# AMU-S03-V00-PSU3V5.net
KiCad netlist of a schematic drawn in Altium Designer
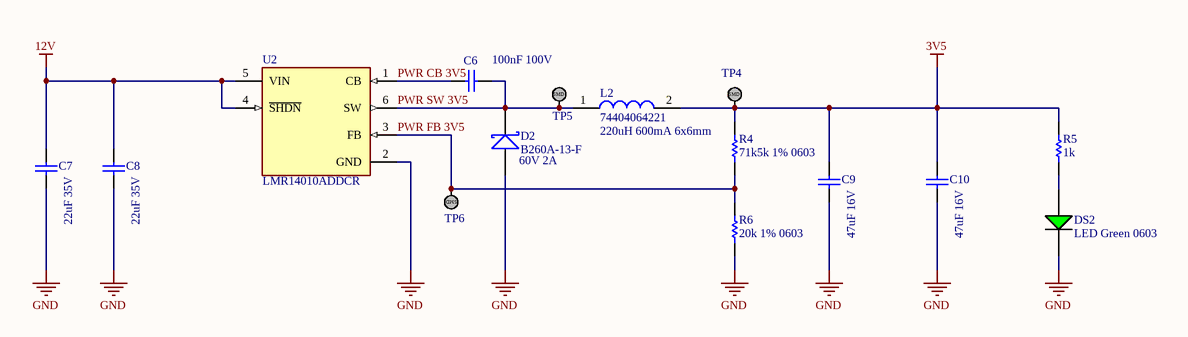
[diagram p0: AMU-S03-V00-PSU3V5.SchDoc]

(export (version "E")
  (design (tool "Eeschema 10.0.6"))
  (components
    (comp (ref "C6")
      (value "100nF 100V")
      (footprint "Cap_Ceramic_0603")
      (description "Capacitor, Ceramic, SMD, 100nF, 100V, 5%, X7R, 0603")
      (libsource (lib "StandardCapacitors") (part "100nF 100V 5% X7R 0603"))
    )
    (comp (ref "C7")
      (value "22uF 35V")
      (footprint "Cap_Ceramic_1206")
      (description "22µF ±20% 35V Ceramic Capacitor X5R 1206 (3216 Metric)")
      (libsource (lib "StandardCapacitors") (part "22uF 35V 20% X5R 1206"))
    )
    (comp (ref "C8")
      (value "22uF 35V")
      (footprint "Cap_Ceramic_1206")
      (description "22µF ±20% 35V Ceramic Capacitor X5R 1206 (3216 Metric)")
      (libsource (lib "StandardCapacitors") (part "22uF 35V 20% X5R 1206"))
    )
    (comp (ref "C9")
      (value "47uF 16V")
      (footprint "Cap_Ceramic_0603")
      (description "Capacitor, Ceramic, SMD, 47uF, 16V, 5%, X7R, 1210")
      (libsource (lib "StandardCapacitors") (part "47uF 16V 10% X7R 1210"))
    )
    (comp (ref "C10")
      (value "47uF 16V")
      (footprint "Cap_Ceramic_0603")
      (description "Capacitor, Ceramic, SMD, 47uF, 16V, 5%, X7R, 1210")
      (libsource (lib "StandardCapacitors") (part "47uF 16V 10% X7R 1210"))
    )
    (comp (ref "D2")
      (value "B260A-13-F")
      (footprint "SMA")
      (description "Diode, Schottky Barrier Rectifier, 60 V, 2 A, B260A-13-F")
      (libsource (lib "QUTMS_DiodeLibrary") (part "B260A-13-F"))
    )
    (comp (ref "DS2")
      (value "LED Green 0603")
      (footprint "LED GREEN 0603")
      (libsource (lib "QUTMS_LEDLibrary") (part "LED Green 0603"))
    )
    (comp (ref "L2")
      (value "74404064221")
      (footprint "Inductor_6x6mm")
      (description "FIXED IND 220UH 660MA 850 MOHM")
      (libsource (lib "QUTMS_InductorLibrary") (part "74404064221"))
    )
    (comp (ref "R4")
      (value "71k5k 1% 0603")
      (footprint "Res_ThinFilm_0603")
      (description "Resistor, SMD, 71k5, 0.1W, 1%, 0603")
      (libsource (lib "StandardResistors") (part "71k5 1% 0603"))
    )
    (comp (ref "R5")
      (value "1k")
      (footprint "Res_ThinFilm_0603")
      (description "Resistor, SMD, 1k, 0.1W, 5%, 0603")
      (libsource (lib "StandardResistors") (part "1k 5% 0603"))
    )
    (comp (ref "R6")
      (value "20k 1% 0603")
      (footprint "Res_ThinFilm_0603")
      (description "Resistor, SMD, 20k, 0.1W, 1%, 0603")
      (libsource (lib "StandardResistors") (part "20k 1% 0603"))
    )
    (comp (ref "TP4")
      (value "TestPoint_SMD")
      (footprint "TestPointSMD")
      (libsource (lib "StandardTest") (part "TestPoint_SMD"))
    )
    (comp (ref "TP5")
      (value "TestPoint_SMD")
      (footprint "TestPointSMD")
      (libsource (lib "StandardTest") (part "TestPoint_SMD"))
    )
    (comp (ref "TP6")
      (value "TestPoint_SMD")
      (footprint "TestPointSMD")
      (libsource (lib "StandardTest") (part "TestPoint_SMD"))
    )
    (comp (ref "U2")
      (value "LMR14010ADDCR")
      (footprint "FP-DDC0006A-MFG")
      (description "IC REG BUCK ADJ 1A TSOT23-6")
      (fields
        (field (name "MANUFACTURER") "Texas Instruments")
        (field (name "OCTOPART") "https://octopart.com/lmr14010addcr-texas+instruments-90753290")
      )
      (libsource (lib "Altium Content Vault") (part "248534993f007311ab4e1890f26e637"))
    )
  )
  (nets
    (net (code "1") (name "/PWR CB 3V5") (class "Default")
      (node (ref "C6") (pin "1") (pinfunction "1_1") (pintype "passive"))
      (node (ref "U2") (pin "1") (pinfunction "CB_1") (pintype "input"))
    )
    (net (code "2") (name "/PWR FB 3V5") (class "Default")
      (node (ref "R4") (pin "1") (pinfunction "1_1") (pintype "passive"))
      (node (ref "R6") (pin "2") (pinfunction "2_2") (pintype "passive"))
      (node (ref "TP6") (pin "1") (pinfunction "1_1") (pintype "passive"))
      (node (ref "U2") (pin "3") (pinfunction "FB_3") (pintype "input"))
    )
    (net (code "3") (name "/PWR SW 3V5") (class "Default")
      (node (ref "C6") (pin "2") (pinfunction "2_2") (pintype "passive"))
      (node (ref "D2") (pin "K") (pinfunction "K_K") (pintype "passive"))
      (node (ref "L2") (pin "1") (pinfunction "1_1") (pintype "passive"))
      (node (ref "TP5") (pin "1") (pinfunction "1_1") (pintype "passive"))
      (node (ref "U2") (pin "6") (pinfunction "SW_6") (pintype "output"))
    )
    (net (code "4") (name "3V5") (class "Default")
      (node (ref "C10") (pin "2") (pinfunction "2_2") (pintype "passive"))
      (node (ref "C9") (pin "2") (pinfunction "2_2") (pintype "passive"))
      (node (ref "L2") (pin "2") (pinfunction "2_2") (pintype "passive"))
      (node (ref "R4") (pin "2") (pinfunction "2_2") (pintype "passive"))
      (node (ref "R5") (pin "2") (pinfunction "2_2") (pintype "passive"))
      (node (ref "TP4") (pin "1") (pinfunction "1_1") (pintype "passive"))
    )
    (net (code "5") (name "12V") (class "Default")
      (node (ref "C7") (pin "2") (pinfunction "2_2") (pintype "passive"))
      (node (ref "C8") (pin "2") (pinfunction "2_2") (pintype "passive"))
      (node (ref "U2") (pin "4") (pinfunction "~{SHDN}_4") (pintype "input"))
      (node (ref "U2") (pin "5") (pinfunction "VIN_5") (pintype "power_in"))
    )
    (net (code "6") (name "GND") (class "Default")
      (node (ref "C10") (pin "1") (pinfunction "1_1") (pintype "passive"))
      (node (ref "C7") (pin "1") (pinfunction "1_1") (pintype "passive"))
      (node (ref "C8") (pin "1") (pinfunction "1_1") (pintype "passive"))
      (node (ref "C9") (pin "1") (pinfunction "1_1") (pintype "passive"))
      (node (ref "D2") (pin "A") (pinfunction "A_A") (pintype "passive"))
      (node (ref "DS2") (pin "2") (pinfunction "C_2") (pintype "passive"))
      (node (ref "R6") (pin "1") (pinfunction "1_1") (pintype "passive"))
      (node (ref "U2") (pin "2") (pinfunction "GND_2") (pintype "power_in"))
    )
    (net (code "7") (name "Net-(DS2-A)") (class "Default")
      (node (ref "DS2") (pin "1") (pinfunction "A_1") (pintype "passive"))
      (node (ref "R5") (pin "1") (pinfunction "1_1") (pintype "passive"))
    )
  )
)
